# Arduino_plate.net
KiCad netlist of a schematic drawn in EAGLE
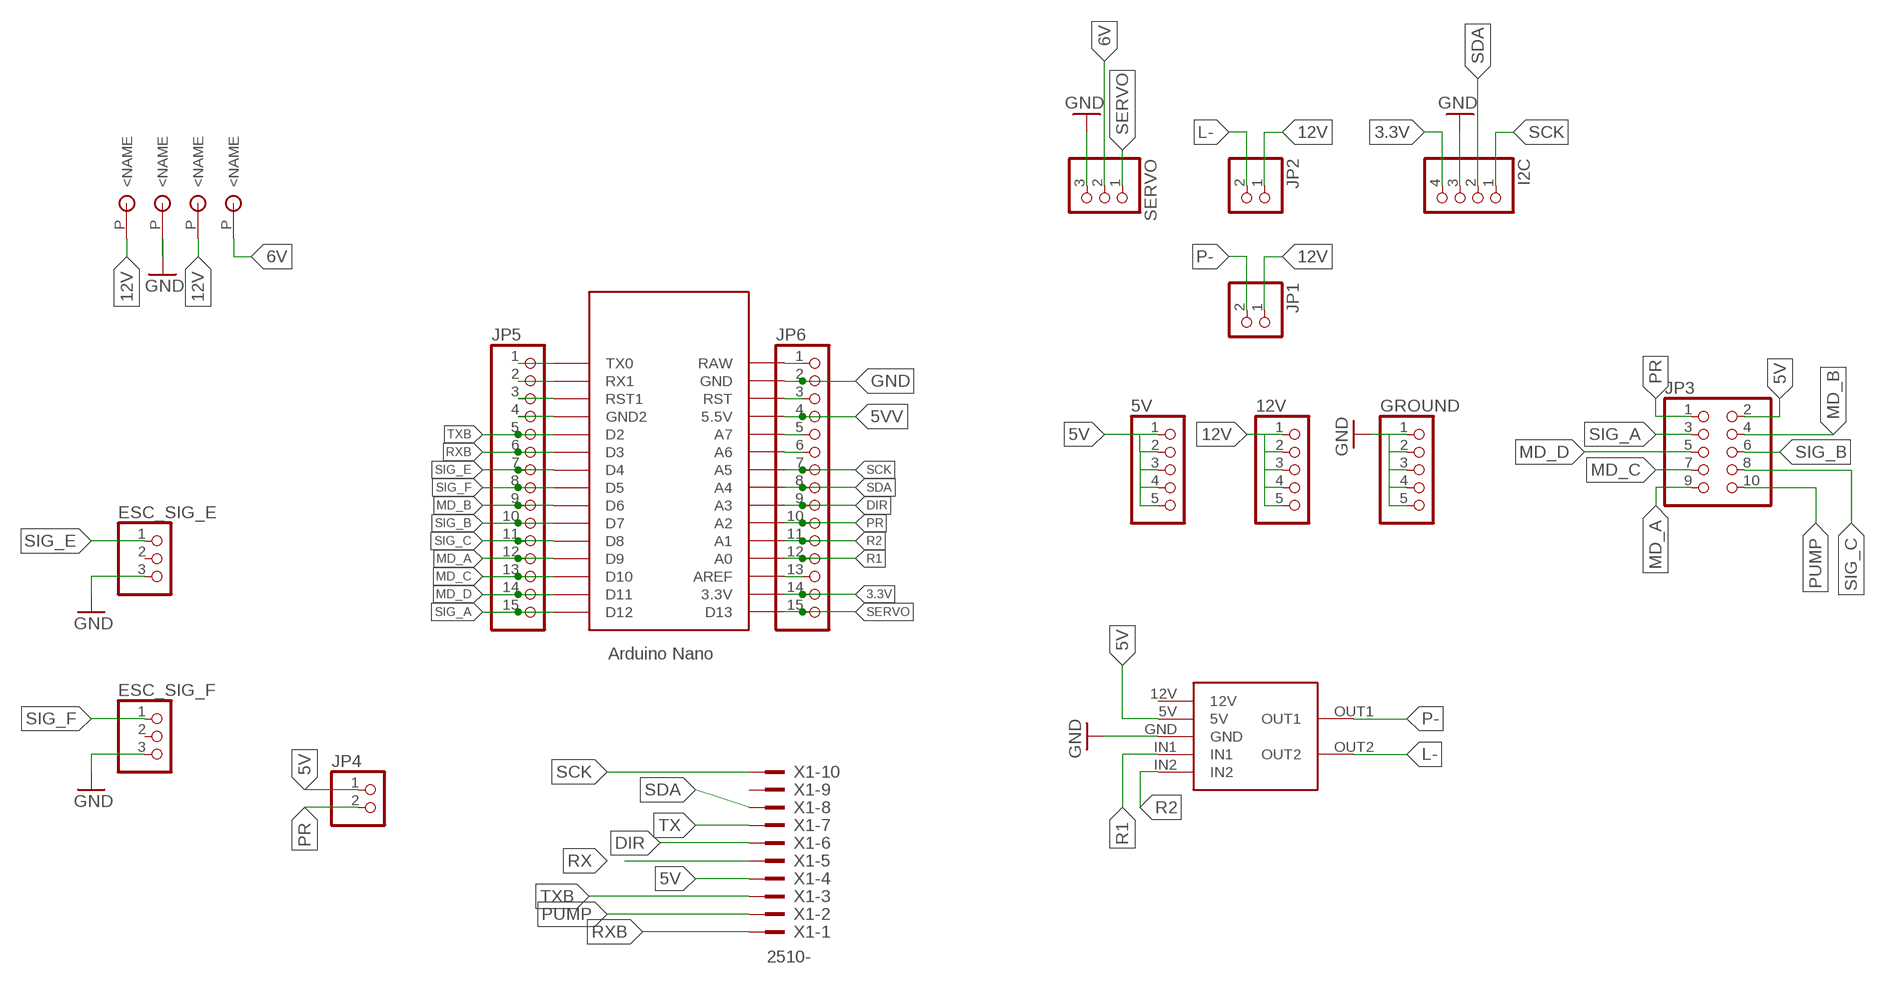
[diagram p0: schematic, sheet 1]

(export (version "E")
  (design (tool "Eeschema 10.0.6"))
  (components
    (comp (ref "5V")
      (value "PINHD-1X5")
      (footprint "eagle-import:1X05")
      (libsource (lib "eagle-import") (part "PINHD-1X5"))
    )
    (comp (ref "6V")
      (value "CU-SPACER")
      (footprint "eagle-import:CU-SPACER")
      (libsource (lib "eagle-import") (part "CU-SPACER"))
    )
    (comp (ref "12")
      (value "CU-SPACER")
      (footprint "eagle-import:CU-SPACER")
      (libsource (lib "eagle-import") (part "CU-SPACER"))
    )
    (comp (ref "12V")
      (value "PINHD-1X5")
      (footprint "eagle-import:1X05")
      (libsource (lib "eagle-import") (part "PINHD-1X5"))
    )
    (comp (ref "ESC_SIG_E")
      (value "PINHD-1X3/90")
      (footprint "eagle-import:1X03_90")
      (libsource (lib "eagle-import") (part "PINHD-1X3/90"))
    )
    (comp (ref "ESC_SIG_F")
      (value "PINHD-1X3/90")
      (footprint "eagle-import:1X03_90")
      (libsource (lib "eagle-import") (part "PINHD-1X3/90"))
    )
    (comp (ref "GND")
      (value "CU-SPACER")
      (footprint "eagle-import:CU-SPACER")
      (libsource (lib "eagle-import") (part "CU-SPACER"))
    )
    (comp (ref "GROUND")
      (value "PINHD-1X5")
      (footprint "eagle-import:1X05")
      (libsource (lib "eagle-import") (part "PINHD-1X5"))
    )
    (comp (ref "I2C")
      (value "PINHD-1X4/90")
      (footprint "eagle-import:1X04_90")
      (libsource (lib "eagle-import") (part "PINHD-1X4/90"))
    )
    (comp (ref "JP1")
      (value "PINHD-1X2/90")
      (footprint "eagle-import:1X02_90")
      (libsource (lib "eagle-import") (part "PINHD-1X2/90"))
    )
    (comp (ref "JP2")
      (value "PINHD-1X2/90")
      (footprint "eagle-import:1X02_90")
      (libsource (lib "eagle-import") (part "PINHD-1X2/90"))
    )
    (comp (ref "JP3")
      (value "PINHD-2X5")
      (footprint "eagle-import:2X05")
      (libsource (lib "eagle-import") (part "PINHD-2X5"))
    )
    (comp (ref "JP4")
      (value "PINHD-1X2/90")
      (footprint "eagle-import:1X02_90")
      (libsource (lib "eagle-import") (part "PINHD-1X2/90"))
    )
    (comp (ref "JP5")
      (value "PINHD-1X15")
      (footprint "eagle-import:1X15")
      (libsource (lib "eagle-import") (part "PINHD-1X15"))
    )
    (comp (ref "JP6")
      (value "PINHD-1X15")
      (footprint "eagle-import:1X15")
      (libsource (lib "eagle-import") (part "PINHD-1X15"))
    )
    (comp (ref "SERVO")
      (value "PINHD-1X3/90")
      (footprint "eagle-import:1X03_90")
      (libsource (lib "eagle-import") (part "PINHD-1X3/90"))
    )
    (comp (ref "U$1")
      (value "NANO")
      (footprint "eagle-import:NANO")
      (libsource (lib "eagle-import") (part "NANO"))
    )
    (comp (ref "U$3")
      (value "2-RELAY-MODULE")
      (footprint "eagle-import:2-RELAY-MODULE")
      (libsource (lib "eagle-import") (part "2-RELAY-MODULE"))
    )
    (comp (ref "U$4")
      (value "CU-SPACER")
      (footprint "eagle-import:CU-SPACER")
      (libsource (lib "eagle-import") (part "CU-SPACER"))
    )
    (comp (ref "X1")
      (value "2510-")
      (footprint "eagle-import:PAK100_2500-10")
      (fields (field (name "MF") "3M") (field (name "MPN") "2510-6002UB"))
      (libsource (lib "eagle-import") (part "2510-"))
    )
  )
  (nets
    (net (code "1") (name "3.3V") (class "Default")
      (node (ref "I2C") (pin "4") (pinfunction "4_4") (pintype "passive"))
      (node (ref "JP6") (pin "14") (pinfunction "14_14") (pintype "passive"))
      (node (ref "U$1") (pin "3.3V") (pinfunction "3.3V_3.3V") (pintype "bidirectional"))
    )
    (net (code "2") (name "5V") (class "Default")
      (node (ref "5V") (pin "1") (pinfunction "1_1") (pintype "passive"))
      (node (ref "5V") (pin "2") (pinfunction "2_2") (pintype "passive"))
      (node (ref "5V") (pin "3") (pinfunction "3_3") (pintype "passive"))
      (node (ref "5V") (pin "4") (pinfunction "4_4") (pintype "passive"))
      (node (ref "5V") (pin "5") (pinfunction "5_5") (pintype "passive"))
      (node (ref "JP3") (pin "2") (pinfunction "2_2") (pintype "passive"))
      (node (ref "JP4") (pin "1") (pinfunction "1_1") (pintype "passive"))
      (node (ref "U$3") (pin "5V") (pinfunction "5V_5V") (pintype "bidirectional"))
      (node (ref "X1") (pin "4") (pinfunction "KL_4") (pintype "passive"))
    )
    (net (code "3") (name "5VV") (class "Default")
      (node (ref "JP6") (pin "4") (pinfunction "4_4") (pintype "passive"))
      (node (ref "U$1") (pin "5V") (pinfunction "5.5V_5V") (pintype "bidirectional"))
    )
    (net (code "4") (name "6V") (class "Default")
      (node (ref "6V") (pin "P") (pinfunction "<NAME_P") (pintype "bidirectional"))
      (node (ref "SERVO") (pin "2") (pinfunction "2_2") (pintype "passive"))
    )
    (net (code "5") (name "12V") (class "Default")
      (node (ref "12") (pin "P") (pinfunction "<NAME_P") (pintype "bidirectional"))
      (node (ref "12V") (pin "1") (pinfunction "1_1") (pintype "passive"))
      (node (ref "12V") (pin "2") (pinfunction "2_2") (pintype "passive"))
      (node (ref "12V") (pin "3") (pinfunction "3_3") (pintype "passive"))
      (node (ref "12V") (pin "4") (pinfunction "4_4") (pintype "passive"))
      (node (ref "12V") (pin "5") (pinfunction "5_5") (pintype "passive"))
      (node (ref "JP1") (pin "1") (pinfunction "1_1") (pintype "passive"))
      (node (ref "JP2") (pin "1") (pinfunction "1_1") (pintype "passive"))
      (node (ref "U$4") (pin "P") (pinfunction "<NAME_P") (pintype "bidirectional"))
    )
    (net (code "6") (name "DIR") (class "Default")
      (node (ref "JP6") (pin "9") (pinfunction "9_9") (pintype "passive"))
      (node (ref "U$1") (pin "A3") (pinfunction "A3_A3") (pintype "bidirectional"))
      (node (ref "X1") (pin "6") (pinfunction "KL_6") (pintype "passive"))
    )
    (net (code "7") (name "GND") (class "Default")
      (node (ref "ESC_SIG_E") (pin "3") (pinfunction "3_3") (pintype "passive"))
      (node (ref "ESC_SIG_F") (pin "3") (pinfunction "3_3") (pintype "passive"))
      (node (ref "GND") (pin "P") (pinfunction "<NAME_P") (pintype "bidirectional"))
      (node (ref "GROUND") (pin "1") (pinfunction "1_1") (pintype "passive"))
      (node (ref "GROUND") (pin "2") (pinfunction "2_2") (pintype "passive"))
      (node (ref "GROUND") (pin "3") (pinfunction "3_3") (pintype "passive"))
      (node (ref "GROUND") (pin "4") (pinfunction "4_4") (pintype "passive"))
      (node (ref "GROUND") (pin "5") (pinfunction "5_5") (pintype "passive"))
      (node (ref "I2C") (pin "3") (pinfunction "3_3") (pintype "passive"))
      (node (ref "JP6") (pin "2") (pinfunction "2_2") (pintype "passive"))
      (node (ref "SERVO") (pin "3") (pinfunction "3_3") (pintype "passive"))
      (node (ref "U$1") (pin "GND") (pinfunction "GND_GND") (pintype "bidirectional"))
      (node (ref "U$3") (pin "GND") (pinfunction "GND_GND") (pintype "bidirectional"))
    )
    (net (code "8") (name "L-") (class "Default")
      (node (ref "JP2") (pin "2") (pinfunction "2_2") (pintype "passive"))
      (node (ref "U$3") (pin "OUT2") (pinfunction "OUT2_OUT2") (pintype "bidirectional"))
    )
    (net (code "9") (name "MD_A") (class "Default")
      (node (ref "JP3") (pin "9") (pinfunction "9_9") (pintype "passive"))
      (node (ref "JP5") (pin "12") (pinfunction "12_12") (pintype "passive"))
      (node (ref "U$1") (pin "D9") (pinfunction "D9_D9") (pintype "bidirectional"))
    )
    (net (code "10") (name "MD_B") (class "Default")
      (node (ref "JP3") (pin "4") (pinfunction "4_4") (pintype "passive"))
      (node (ref "JP5") (pin "9") (pinfunction "9_9") (pintype "passive"))
      (node (ref "U$1") (pin "D6") (pinfunction "D6_D6") (pintype "bidirectional"))
    )
    (net (code "11") (name "MD_C") (class "Default")
      (node (ref "JP3") (pin "7") (pinfunction "7_7") (pintype "passive"))
      (node (ref "JP5") (pin "13") (pinfunction "13_13") (pintype "passive"))
      (node (ref "U$1") (pin "D10") (pinfunction "D10_D10") (pintype "bidirectional"))
    )
    (net (code "12") (name "MD_D") (class "Default")
      (node (ref "JP3") (pin "5") (pinfunction "5_5") (pintype "passive"))
      (node (ref "JP5") (pin "14") (pinfunction "14_14") (pintype "passive"))
      (node (ref "U$1") (pin "D11") (pinfunction "D11_D11") (pintype "bidirectional"))
    )
    (net (code "13") (name "Net-(JP5-Pad3)") (class "Default")
      (node (ref "JP5") (pin "3") (pinfunction "3_3") (pintype "passive"))
      (node (ref "U$1") (pin "RST1") (pinfunction "RST1_RST1") (pintype "bidirectional"))
    )
    (net (code "14") (name "Net-(JP6-Pad1)") (class "Default")
      (node (ref "JP6") (pin "1") (pinfunction "1_1") (pintype "passive"))
      (node (ref "U$1") (pin "RAW") (pinfunction "RAW_RAW") (pintype "bidirectional"))
    )
    (net (code "15") (name "Net-(JP6-Pad3)") (class "Default")
      (node (ref "JP6") (pin "3") (pinfunction "3_3") (pintype "passive"))
      (node (ref "U$1") (pin "RST") (pinfunction "RST_RST") (pintype "bidirectional"))
    )
    (net (code "16") (name "Net-(JP6-Pad5)") (class "Default")
      (node (ref "JP6") (pin "5") (pinfunction "5_5") (pintype "passive"))
      (node (ref "U$1") (pin "A7") (pinfunction "A7_A7") (pintype "bidirectional"))
    )
    (net (code "17") (name "Net-(JP6-Pad6)") (class "Default")
      (node (ref "JP6") (pin "6") (pinfunction "6_6") (pintype "passive"))
      (node (ref "U$1") (pin "A6") (pinfunction "A6_A6") (pintype "bidirectional"))
    )
    (net (code "18") (name "Net-(JP6-Pad13)") (class "Default")
      (node (ref "JP6") (pin "13") (pinfunction "13_13") (pintype "passive"))
      (node (ref "U$1") (pin "AREF") (pinfunction "AREF_AREF") (pintype "bidirectional"))
    )
    (net (code "19") (name "Net-(U$1-GND2)") (class "Default")
      (node (ref "JP5") (pin "4") (pinfunction "4_4") (pintype "passive"))
      (node (ref "U$1") (pin "GND1") (pinfunction "GND2_GND1") (pintype "bidirectional"))
    )
    (net (code "20") (name "P-") (class "Default")
      (node (ref "JP1") (pin "2") (pinfunction "2_2") (pintype "passive"))
      (node (ref "U$3") (pin "OUT1") (pinfunction "OUT1_OUT1") (pintype "bidirectional"))
    )
    (net (code "21") (name "PR") (class "Default")
      (node (ref "JP3") (pin "1") (pinfunction "1_1") (pintype "passive"))
      (node (ref "JP4") (pin "2") (pinfunction "2_2") (pintype "passive"))
      (node (ref "JP6") (pin "10") (pinfunction "10_10") (pintype "passive"))
      (node (ref "U$1") (pin "A2") (pinfunction "A2_A2") (pintype "bidirectional"))
    )
    (net (code "22") (name "PUMP") (class "Default")
      (node (ref "JP3") (pin "10") (pinfunction "10_10") (pintype "passive"))
      (node (ref "X1") (pin "2") (pinfunction "KL_2") (pintype "passive"))
    )
    (net (code "23") (name "R1") (class "Default")
      (node (ref "JP6") (pin "12") (pinfunction "12_12") (pintype "passive"))
      (node (ref "U$1") (pin "A0") (pinfunction "A0_A0") (pintype "bidirectional"))
      (node (ref "U$3") (pin "IN1") (pinfunction "IN1_IN1") (pintype "bidirectional"))
    )
    (net (code "24") (name "R2") (class "Default")
      (node (ref "JP6") (pin "11") (pinfunction "11_11") (pintype "passive"))
      (node (ref "U$1") (pin "A1") (pinfunction "A1_A1") (pintype "bidirectional"))
      (node (ref "U$3") (pin "IN2") (pinfunction "IN2_IN2") (pintype "bidirectional"))
    )
    (net (code "25") (name "RX") (class "Default")
      (node (ref "JP5") (pin "2") (pinfunction "2_2") (pintype "passive"))
      (node (ref "U$1") (pin "RX1") (pinfunction "RX1_RX1") (pintype "bidirectional"))
      (node (ref "X1") (pin "5") (pinfunction "KL_5") (pintype "passive"))
    )
    (net (code "26") (name "RXB") (class "Default")
      (node (ref "JP5") (pin "6") (pinfunction "6_6") (pintype "passive"))
      (node (ref "U$1") (pin "D3") (pinfunction "D3_D3") (pintype "bidirectional"))
      (node (ref "X1") (pin "1") (pinfunction "KL_1") (pintype "passive"))
    )
    (net (code "27") (name "SCK") (class "Default")
      (node (ref "I2C") (pin "1") (pinfunction "1_1") (pintype "passive"))
      (node (ref "JP6") (pin "7") (pinfunction "7_7") (pintype "passive"))
      (node (ref "U$1") (pin "A5") (pinfunction "A5_A5") (pintype "bidirectional"))
      (node (ref "X1") (pin "10") (pinfunction "KL_10") (pintype "passive"))
    )
    (net (code "28") (name "SDA") (class "Default")
      (node (ref "I2C") (pin "2") (pinfunction "2_2") (pintype "passive"))
      (node (ref "JP6") (pin "8") (pinfunction "8_8") (pintype "passive"))
      (node (ref "U$1") (pin "A4") (pinfunction "A4_A4") (pintype "bidirectional"))
      (node (ref "X1") (pin "8") (pinfunction "KL_8") (pintype "passive"))
    )
    (net (code "29") (name "SERVO") (class "Default")
      (node (ref "JP6") (pin "15") (pinfunction "15_15") (pintype "passive"))
      (node (ref "SERVO") (pin "1") (pinfunction "1_1") (pintype "passive"))
      (node (ref "U$1") (pin "D13") (pinfunction "D13_D13") (pintype "bidirectional"))
    )
    (net (code "30") (name "SIG_A") (class "Default")
      (node (ref "JP3") (pin "3") (pinfunction "3_3") (pintype "passive"))
      (node (ref "JP5") (pin "15") (pinfunction "15_15") (pintype "passive"))
      (node (ref "U$1") (pin "D12") (pinfunction "D12_D12") (pintype "bidirectional"))
    )
    (net (code "31") (name "SIG_B") (class "Default")
      (node (ref "JP3") (pin "6") (pinfunction "6_6") (pintype "passive"))
      (node (ref "JP5") (pin "10") (pinfunction "10_10") (pintype "passive"))
      (node (ref "U$1") (pin "D7") (pinfunction "D7_D7") (pintype "bidirectional"))
    )
    (net (code "32") (name "SIG_C") (class "Default")
      (node (ref "JP3") (pin "8") (pinfunction "8_8") (pintype "passive"))
      (node (ref "JP5") (pin "11") (pinfunction "11_11") (pintype "passive"))
      (node (ref "U$1") (pin "D8") (pinfunction "D8_D8") (pintype "bidirectional"))
    )
    (net (code "33") (name "SIG_E") (class "Default")
      (node (ref "ESC_SIG_E") (pin "1") (pinfunction "1_1") (pintype "passive"))
      (node (ref "JP5") (pin "7") (pinfunction "7_7") (pintype "passive"))
      (node (ref "U$1") (pin "D4") (pinfunction "D4_D4") (pintype "bidirectional"))
    )
    (net (code "34") (name "SIG_F") (class "Default")
      (node (ref "ESC_SIG_F") (pin "1") (pinfunction "1_1") (pintype "passive"))
      (node (ref "JP5") (pin "8") (pinfunction "8_8") (pintype "passive"))
      (node (ref "U$1") (pin "D5") (pinfunction "D5_D5") (pintype "bidirectional"))
    )
    (net (code "35") (name "TX") (class "Default")
      (node (ref "JP5") (pin "1") (pinfunction "1_1") (pintype "passive"))
      (node (ref "U$1") (pin "TX0") (pinfunction "TX0_TX0") (pintype "bidirectional"))
      (node (ref "X1") (pin "7") (pinfunction "KL_7") (pintype "passive"))
    )
    (net (code "36") (name "TXB") (class "Default")
      (node (ref "JP5") (pin "5") (pinfunction "5_5") (pintype "passive"))
      (node (ref "U$1") (pin "D2") (pinfunction "D2_D2") (pintype "bidirectional"))
      (node (ref "X1") (pin "3") (pinfunction "KL_3") (pintype "passive"))
    )
    (net (code "37") (name "unconnected-(ESC_SIG_E-Pad2)") (class "Default")
      (node (ref "ESC_SIG_E") (pin "2") (pinfunction "2_2") (pintype "passive"))
    )
    (net (code "38") (name "unconnected-(ESC_SIG_F-Pad2)") (class "Default")
      (node (ref "ESC_SIG_F") (pin "2") (pinfunction "2_2") (pintype "passive"))
    )
    (net (code "39") (name "unconnected-(U$1-PadICSP1)") (class "Default")
      (node (ref "U$1") (pin "ICSP1") (pinfunction "ICSP1_ICSP1") (pintype "bidirectional"))
    )
    (net (code "40") (name "unconnected-(U$1-PadICSP2)") (class "Default")
      (node (ref "U$1") (pin "ICSP2") (pinfunction "ICSP2_ICSP2") (pintype "bidirectional"))
    )
    (net (code "41") (name "unconnected-(U$1-PadICSP3)") (class "Default")
      (node (ref "U$1") (pin "ICSP3") (pinfunction "ICSP3_ICSP3") (pintype "bidirectional"))
    )
    (net (code "42") (name "unconnected-(U$1-PadICSP4)") (class "Default")
      (node (ref "U$1") (pin "ICSP4") (pinfunction "ICSP4_ICSP4") (pintype "bidirectional"))
    )
    (net (code "43") (name "unconnected-(U$1-PadICSP5)") (class "Default")
      (node (ref "U$1") (pin "ICSP5") (pinfunction "ICSP5_ICSP5") (pintype "bidirectional"))
    )
    (net (code "44") (name "unconnected-(U$1-PadICSP6)") (class "Default")
      (node (ref "U$1") (pin "ICSP6") (pinfunction "ICSP6_ICSP6") (pintype "bidirectional"))
    )
    (net (code "45") (name "unconnected-(U$3-Pad12V)") (class "Default")
      (node (ref "U$3") (pin "12V") (pinfunction "12V_12V") (pintype "bidirectional"))
    )
    (net (code "46") (name "unconnected-(X1J-KL-Pad9)") (class "Default")
      (node (ref "X1") (pin "9") (pinfunction "KL_9") (pintype "passive"))
    )
  )
)
